# vgnd.net
KiCad netlist of a schematic drawn in EAGLE
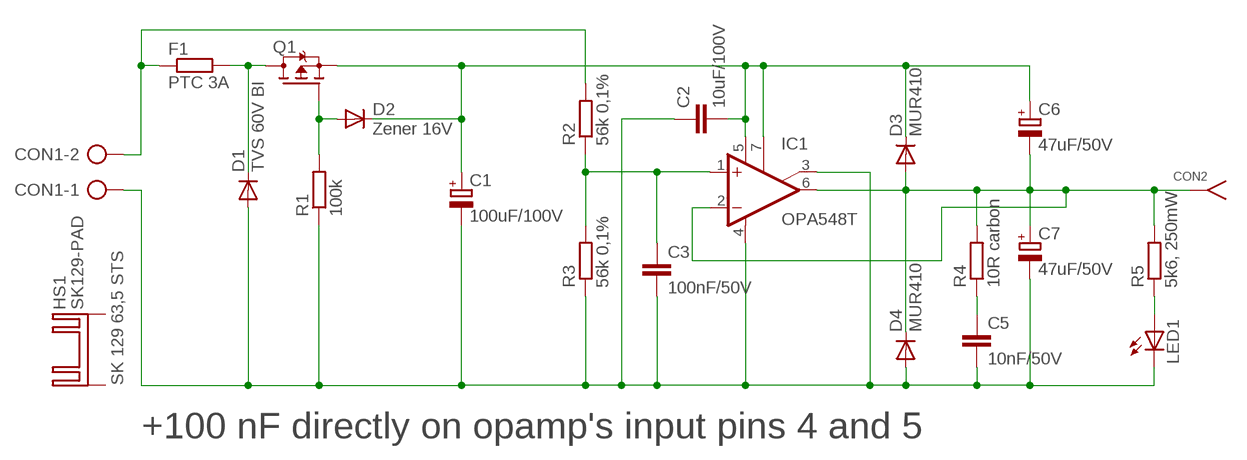
[diagram p0: schematic, sheet 1]

(export (version "E")
  (design (tool "Eeschema 10.0.6"))
  (components
    (comp (ref "C1")
      (value "100uF/100V")
      (footprint "eagle-import:E5-10,5")
      (libsource (lib "eagle-import") (part "CPOL-EUE5-10.5"))
    )
    (comp (ref "C2")
      (value "10uF/100V")
      (footprint "eagle-import:C2220K")
      (libsource (lib "eagle-import") (part "C-EUC2220K"))
    )
    (comp (ref "C3")
      (value "100nF/50V")
      (footprint "eagle-import:C0603")
      (libsource (lib "eagle-import") (part "C-EUC0603"))
    )
    (comp (ref "C5")
      (value "10nF/50V")
      (footprint "eagle-import:C0603")
      (libsource (lib "eagle-import") (part "C-EUC0603"))
    )
    (comp (ref "C6")
      (value "47uF/50V")
      (footprint "eagle-import:E2,5-7")
      (libsource (lib "eagle-import") (part "CPOL-EUE2.5-7"))
    )
    (comp (ref "C7")
      (value "47uF/50V")
      (footprint "eagle-import:E2,5-7")
      (libsource (lib "eagle-import") (part "CPOL-EUE2.5-7"))
    )
    (comp (ref "CON1")
      (value "AK500/2")
      (footprint "eagle-import:AK500_2")
      (libsource (lib "eagle-import") (part "AK500/2"))
    )
    (comp (ref "CON2")
      (value "FCR7350")
      (footprint "eagle-import:BANANA-PCB-S16N")
      (libsource (lib "eagle-import") (part "FCR7350"))
    )
    (comp (ref "D1")
      (value "TVS 60V BI")
      (footprint "eagle-import:SMC")
      (libsource (lib "eagle-import") (part "DIODE-SMC"))
    )
    (comp (ref "D2")
      (value "Zener 16V")
      (footprint "eagle-import:SOD323-R")
      (libsource (lib "eagle-import") (part "DIODE-SOD323-R"))
    )
    (comp (ref "D3")
      (value "MUR410")
      (footprint "eagle-import:DO201-15")
      (libsource (lib "eagle-import") (part "DIODE-DO201-15"))
    )
    (comp (ref "D4")
      (value "MUR410")
      (footprint "eagle-import:DO201-15")
      (libsource (lib "eagle-import") (part "DIODE-DO201-15"))
    )
    (comp (ref "F1")
      (value "PTC 3A")
      (footprint "eagle-import:0309_10")
      (libsource (lib "eagle-import") (part "R-EU_0309/10"))
    )
    (comp (ref "HS1")
      (value "SK129-PAD")
      (footprint "eagle-import:SK129")
      (fields (field (name "ITEM") "SK 129 63,5 STS"))
      (libsource (lib "eagle-import") (part "SK129-PAD"))
    )
    (comp (ref "IC1")
      (value "OPA548T")
      (footprint "eagle-import:TO220-7")
      (fields (field (name "MF") "TEXAS INSTRUMENTS"))
      (libsource (lib "eagle-import") (part "OPA548T"))
    )
    (comp (ref "LED1")
      (value "LEDCHIPLED_0603")
      (footprint "eagle-import:CHIPLED_0603")
      (libsource (lib "eagle-import") (part "LEDCHIPLED_0603"))
    )
    (comp (ref "Q1")
      (value "FDD4141TO252")
      (footprint "eagle-import:TO252")
      (libsource (lib "eagle-import") (part "FDD4141TO252"))
    )
    (comp (ref "R1")
      (value "100k")
      (footprint "eagle-import:R0603")
      (libsource (lib "eagle-import") (part "resistor_R-EU_R0603"))
    )
    (comp (ref "R2")
      (value "56k 0,1%")
      (footprint "eagle-import:R0603")
      (libsource (lib "eagle-import") (part "resistor_R-EU_R0603"))
    )
    (comp (ref "R3")
      (value "56k 0,1%")
      (footprint "eagle-import:R0603")
      (libsource (lib "eagle-import") (part "resistor_R-EU_R0603"))
    )
    (comp (ref "R4")
      (value "10R carbon")
      (footprint "eagle-import:0207_10")
      (libsource (lib "eagle-import") (part "resistor_R-EU_0207/10"))
    )
    (comp (ref "R5")
      (value "5k6, 250mW")
      (footprint "eagle-import:M1206")
      (libsource (lib "eagle-import") (part "R-EU_M1206"))
    )
  )
  (nets
    (net (code "1") (name "Net-(C5-Pad1)") (class "Default")
      (node (ref "C5") (pin "1") (pinfunction "1_1") (pintype "passive"))
      (node (ref "R4") (pin "1") (pinfunction "1_1") (pintype "passive"))
    )
    (net (code "2") (name "Net-(CON1A-KL)") (class "Default")
      (node (ref "C1") (pin "-") (pinfunction "-_-") (pintype "passive"))
      (node (ref "C2") (pin "1") (pinfunction "1_1") (pintype "passive"))
      (node (ref "C3") (pin "2") (pinfunction "2_2") (pintype "passive"))
      (node (ref "C5") (pin "2") (pinfunction "2_2") (pintype "passive"))
      (node (ref "C7") (pin "-") (pinfunction "-_-") (pintype "passive"))
      (node (ref "CON1") (pin "1") (pinfunction "KL_1") (pintype "passive"))
      (node (ref "D1") (pin "A") (pinfunction "A_A") (pintype "passive"))
      (node (ref "D4") (pin "A") (pinfunction "A_A") (pintype "passive"))
      (node (ref "IC1") (pin "3") (pinfunction "ILIM_3") (pintype "input"))
      (node (ref "IC1") (pin "4") (pinfunction "V-_4") (pintype "power_in"))
      (node (ref "LED1") (pin "C") (pinfunction "C_C") (pintype "passive"))
      (node (ref "R1") (pin "1") (pinfunction "1_1") (pintype "passive"))
      (node (ref "R3") (pin "1") (pinfunction "1_1") (pintype "passive"))
    )
    (net (code "3") (name "Net-(CON1B-KL)") (class "Default")
      (node (ref "CON1") (pin "2") (pinfunction "KL_2") (pintype "passive"))
      (node (ref "F1") (pin "1") (pinfunction "1_1") (pintype "passive"))
      (node (ref "R2") (pin "2") (pinfunction "2_2") (pintype "passive"))
    )
    (net (code "4") (name "Net-(IC1-+IN)") (class "Default")
      (node (ref "C3") (pin "1") (pinfunction "1_1") (pintype "passive"))
      (node (ref "IC1") (pin "1") (pinfunction "+IN_1") (pintype "input"))
      (node (ref "R2") (pin "1") (pinfunction "1_1") (pintype "passive"))
      (node (ref "R3") (pin "2") (pinfunction "2_2") (pintype "passive"))
    )
    (net (code "5") (name "Net-(IC1--IN)") (class "Default")
      (node (ref "C6") (pin "-") (pinfunction "-_-") (pintype "passive"))
      (node (ref "C7") (pin "+") (pinfunction "+_+") (pintype "passive"))
      (node (ref "CON2") (pin "P$1") (pinfunction "CON$1_P$1") (pintype "bidirectional"))
      (node (ref "CON2") (pin "P$2") (pinfunction "CON$1_P$2") (pintype "bidirectional"))
      (node (ref "CON2") (pin "P$3") (pinfunction "CON$1_P$3") (pintype "bidirectional"))
      (node (ref "CON2") (pin "P$4") (pinfunction "CON$1_P$4") (pintype "bidirectional"))
      (node (ref "CON2") (pin "P$5") (pinfunction "CON$1_P$5") (pintype "bidirectional"))
      (node (ref "D3") (pin "A") (pinfunction "A_A") (pintype "passive"))
      (node (ref "D4") (pin "C") (pinfunction "C_C") (pintype "passive"))
      (node (ref "IC1") (pin "2") (pinfunction "-IN_2") (pintype "input"))
      (node (ref "IC1") (pin "6") (pinfunction "OUT_6") (pintype "output"))
      (node (ref "R4") (pin "2") (pinfunction "2_2") (pintype "passive"))
      (node (ref "R5") (pin "2") (pinfunction "2_2") (pintype "passive"))
    )
    (net (code "6") (name "Net-(IC1-E{slash}S)") (class "Default")
      (node (ref "C1") (pin "+") (pinfunction "+_+") (pintype "passive"))
      (node (ref "C2") (pin "2") (pinfunction "2_2") (pintype "passive"))
      (node (ref "C6") (pin "+") (pinfunction "+_+") (pintype "passive"))
      (node (ref "D2") (pin "C") (pinfunction "C_C") (pintype "passive"))
      (node (ref "D3") (pin "C") (pinfunction "C_C") (pintype "passive"))
      (node (ref "IC1") (pin "5") (pinfunction "V+_5") (pintype "power_in"))
      (node (ref "IC1") (pin "7") (pinfunction "E/S_7") (pintype "bidirectional"))
      (node (ref "Q1") (pin "2") (pinfunction "S_2") (pintype "passive"))
    )
    (net (code "7") (name "Net-(LED1-PadA)") (class "Default")
      (node (ref "LED1") (pin "A") (pinfunction "A_A") (pintype "passive"))
      (node (ref "R5") (pin "1") (pinfunction "1_1") (pintype "passive"))
    )
    (net (code "8") (name "Net-(Q1-D)") (class "Default")
      (node (ref "D1") (pin "C") (pinfunction "C_C") (pintype "passive"))
      (node (ref "F1") (pin "2") (pinfunction "2_2") (pintype "passive"))
      (node (ref "Q1") (pin "3") (pinfunction "D_3") (pintype "passive"))
    )
    (net (code "9") (name "Net-(Q1-G)") (class "Default")
      (node (ref "D2") (pin "A") (pinfunction "A_A") (pintype "passive"))
      (node (ref "Q1") (pin "1") (pinfunction "G_1") (pintype "passive"))
      (node (ref "R1") (pin "2") (pinfunction "2_2") (pintype "passive"))
    )
    (net (code "10") (name "unconnected-(HS1-K-PadA2,5)") (class "Default")
      (node (ref "HS1") (pin "A2,5") (pinfunction "K_A2,5") (pintype "passive"))
    )
    (net (code "11") (name "unconnected-(HS1-K-PadB2,5)") (class "Default")
      (node (ref "HS1") (pin "B2,5") (pinfunction "K_B2,5") (pintype "passive"))
    )
  )
)
